# TOP.net
KiCad netlist of a schematic drawn in Altium Designer
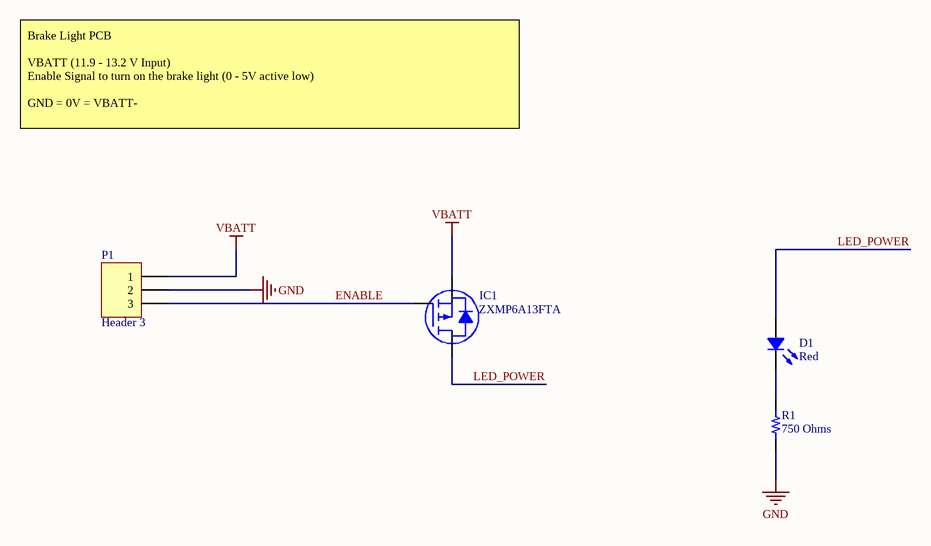
[diagram p0: TOP.SchDoc]

(export (version "E")
  (design (tool "Eeschema 10.0.6"))
  (components
    (comp (ref "D1")
      (value "Red")
      (footprint "LED 1206_3216 RED")
      (description "LED SMD")
      (fields (field (name "PART NUMBER") "APTR3216SECK/J3-PRV") (field (name "MANUFACTURER") "Kingbright"))
      (libsource (lib "Celestial") (part "LED"))
    )
    (comp (ref "IC1")
      (value "ZXMP6A13FTA")
      (footprint "DIODES SOT-23-3")
      (description "MOSFET P-CH 60V 0.9A SOT23-3")
      (fields (field (name "MANUFACTURER") "Diodes Incorporated"))
      (libsource (lib "Celestial") (part "DIODES MOSFET P-CH SOT-23-3"))
    )
    (comp (ref "P1")
      (value "Header 3")
      (footprint "HDR1X3")
      (description "Header, 3-Pin")
      (fields (field (name "PUBLISHER") "Altium Limited"))
      (libsource (lib "Miscellaneous Connectors") (part "Header 3"))
    )
    (comp (ref "R1")
      (value "750 Ohms")
      (footprint "RES 0603_1608")
      (description "RES SMD 750 OHM 0.1% 1/5W 0603")
      (fields
        (field (name "PART NUMBER") "ERJ-PB3B7500V")
        (field (name "MANUFACTURER") "Panasonic Electronic Components")
      )
      (libsource (lib "Celestial") (part "Resistor"))
    )
  )
  (nets
    (net (code "1") (name "/ENABLE") (class "Default")
      (node (ref "IC1") (pin "1") (pinfunction "G_1") (pintype "passive"))
      (node (ref "P1") (pin "3") (pinfunction "3_3") (pintype "passive"))
    )
    (net (code "2") (name "/LED_POWER") (class "Default")
      (node (ref "D1") (pin "1") (pinfunction "1_1") (pintype "passive"))
      (node (ref "IC1") (pin "3") (pinfunction "D_3") (pintype "passive"))
    )
    (net (code "3") (name "GND") (class "Default")
      (node (ref "P1") (pin "2") (pinfunction "2_2") (pintype "passive"))
      (node (ref "R1") (pin "1") (pinfunction "1_1") (pintype "passive"))
    )
    (net (code "4") (name "Net-(D1-Pad2)") (class "Default")
      (node (ref "D1") (pin "2") (pinfunction "2_2") (pintype "passive"))
      (node (ref "R1") (pin "2") (pinfunction "2_2") (pintype "passive"))
    )
    (net (code "5") (name "VBATT") (class "Default")
      (node (ref "IC1") (pin "2") (pinfunction "S_2") (pintype "passive"))
      (node (ref "P1") (pin "1") (pinfunction "1_1") (pintype "passive"))
    )
  )
)
